# DCP_DC_DC.net
KiCad netlist of a schematic drawn in Altium Designer
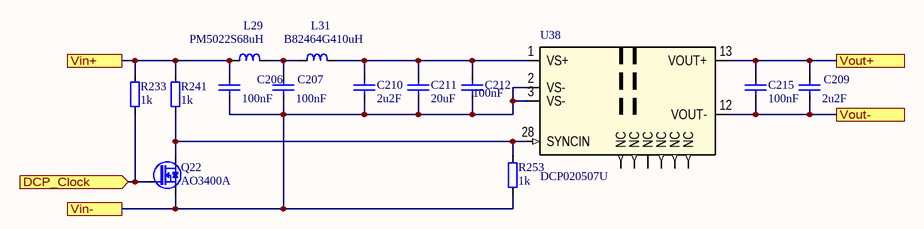
[diagram p0: DCP_DC_DC.SchDoc]

(export (version "E")
  (design (tool "Eeschema 10.0.6"))
  (components
    (comp (ref "C206")
      (value "100nF")
      (footprint "SMD0805CAP")
      (description "Чип конденсатор 0805")
      (fields (field (name "VOLTAGE") "25V") (field (name "TOLERANCE") "20%"))
      (libsource (lib "DDSintLib") (part "C0805"))
    )
    (comp (ref "C207")
      (value "100nF")
      (footprint "SMD0805CAP")
      (description "Чип конденсатор 0805")
      (fields (field (name "VOLTAGE") "25V") (field (name "TOLERANCE") "20%"))
      (libsource (lib "DDSintLib") (part "C0805"))
    )
    (comp (ref "C209")
      (value "2u2F")
      (footprint "SMD0805CAP")
      (description "Чип конденсатор 0805")
      (fields (field (name "VOLTAGE") "25V") (field (name "TOLERANCE") "20%"))
      (libsource (lib "DDSintLib") (part "C0805"))
    )
    (comp (ref "C210")
      (value "2u2F")
      (footprint "SMD0805CAP")
      (description "Чип конденсатор 0805")
      (fields (field (name "VOLTAGE") "25V") (field (name "TOLERANCE") "20%"))
      (libsource (lib "DDSintLib") (part "C0805"))
    )
    (comp (ref "C211")
      (value "20uF")
      (footprint "CAPC1206")
      (description "Чип конденсатор 0805")
      (fields (field (name "VOLTAGE") "16V") (field (name "TOLERANCE") "1%"))
      (libsource (lib "DDSintLib") (part "C1206"))
    )
    (comp (ref "C212")
      (value "100nF")
      (footprint "SMD0805CAP")
      (description "Чип конденсатор 0805")
      (fields (field (name "VOLTAGE") "25V") (field (name "TOLERANCE") "20%"))
      (libsource (lib "DDSintLib") (part "C0805"))
    )
    (comp (ref "C215")
      (value "100nF")
      (footprint "SMD0805CAP")
      (description "Чип конденсатор 0805")
      (fields (field (name "VOLTAGE") "25V") (field (name "TOLERANCE") "20%"))
      (libsource (lib "DDSintLib") (part "C0805"))
    )
    (comp (ref "L29")
      (value "PM5022S68uH")
      (footprint "IND_Bourns_PM5022S")
      (description "SMD Дроссель")
      (fields (field (name "VOLTAGE") "2") (field (name "TOLERANCE") "20%"))
      (libsource (lib "DDS1") (part "IND_BOURNS_PM5022S"))
    )
    (comp (ref "L31")
      (value "B82464G410uH")
      (footprint "IND_COILCRAFT_MSS1038")
      (description "SMD Дроссель")
      (fields (field (name "VOLTAGE") "2") (field (name "TOLERANCE") "20%"))
      (libsource (lib "DDSintLib") (part "B82464G4"))
    )
    (comp (ref "Q22")
      (value "AO3400A")
      (footprint "SOT95P229X119-3N")
      (description "NMOS")
      (fields (field (name "VOLTAGE") "30V"))
      (libsource (lib "DDSintLib") (part "AO3400A"))
    )
    (comp (ref "R233")
      (value "1k")
      (footprint "SMD0805RES")
      (description "Чип резистор 0805")
      (fields (field (name "TOLERANCE") "1%"))
      (libsource (lib "DDSintLib") (part "R0805"))
    )
    (comp (ref "R241")
      (value "1k")
      (footprint "SMD0805RES")
      (description "Чип резистор 0805")
      (fields (field (name "TOLERANCE") "1%"))
      (libsource (lib "DDSintLib") (part "R0805"))
    )
    (comp (ref "R253")
      (value "1k")
      (footprint "SMD0805RES")
      (description "Чип резистор 0805")
      (fields (field (name "TOLERANCE") "1%"))
      (libsource (lib "DDSintLib") (part "R0805"))
    )
    (comp (ref "U38")
      (value "DCP020507U")
      (footprint "SOIC127P1033X265-12_28N")
      (description "DC/DC xxV to isolated  yyV")
      (fields
        (field (name "VOLTAGE") "7V")
        (field (name "COPYRIGHT") "Copyright (C) 2022 Ultra Librarian. All rights reserved.")
      )
      (libsource (lib "DDS1") (part "DCP02xxyyU"))
    )
  )
  (nets
    (net (code "1") (name "/DCP_Clock") (class "Default")
      (node (ref "Q22") (pin "1") (pinfunction "G_1") (pintype "passive"))
      (node (ref "R233") (pin "2") (pinfunction "2_2") (pintype "passive"))
    )
    (net (code "2") (name "/Vin+") (class "Default")
      (node (ref "C206") (pin "2") (pinfunction "2_2") (pintype "passive"))
      (node (ref "L29") (pin "1") (pinfunction "1_1") (pintype "passive"))
      (node (ref "R233") (pin "1") (pinfunction "1_1") (pintype "passive"))
      (node (ref "R241") (pin "1") (pinfunction "1_1") (pintype "passive"))
    )
    (net (code "3") (name "/Vin-") (class "Default")
      (node (ref "C206") (pin "1") (pinfunction "1_1") (pintype "passive"))
      (node (ref "C207") (pin "1") (pinfunction "1_1") (pintype "passive"))
      (node (ref "C210") (pin "1") (pinfunction "1_1") (pintype "passive"))
      (node (ref "C211") (pin "1") (pinfunction "1_1") (pintype "passive"))
      (node (ref "C212") (pin "1") (pinfunction "1_1") (pintype "passive"))
      (node (ref "Q22") (pin "2") (pinfunction "S_2") (pintype "passive"))
      (node (ref "R253") (pin "2") (pinfunction "2_2") (pintype "passive"))
      (node (ref "U38") (pin "2") (pinfunction "VS-_2") (pintype "power_in"))
      (node (ref "U38") (pin "3") (pinfunction "VS-_3") (pintype "power_in"))
    )
    (net (code "4") (name "/Vout+") (class "Default")
      (node (ref "C209") (pin "2") (pinfunction "2_2") (pintype "passive"))
      (node (ref "C215") (pin "2") (pinfunction "2_2") (pintype "passive"))
      (node (ref "U38") (pin "13") (pinfunction "VOUT+_13") (pintype "power_in"))
    )
    (net (code "5") (name "/Vout-") (class "Default")
      (node (ref "C209") (pin "1") (pinfunction "1_1") (pintype "passive"))
      (node (ref "C215") (pin "1") (pinfunction "1_1") (pintype "passive"))
      (node (ref "U38") (pin "12") (pinfunction "VOUT-_12") (pintype "power_in"))
    )
    (net (code "6") (name "Net-(C207-Pad2)") (class "Default")
      (node (ref "C207") (pin "2") (pinfunction "2_2") (pintype "passive"))
      (node (ref "L29") (pin "2") (pinfunction "2_2") (pintype "passive"))
      (node (ref "L31") (pin "1") (pinfunction "1_1") (pintype "passive"))
    )
    (net (code "7") (name "Net-(Q22-D)") (class "Default")
      (node (ref "Q22") (pin "3") (pinfunction "D_3") (pintype "passive"))
      (node (ref "R241") (pin "2") (pinfunction "2_2") (pintype "passive"))
      (node (ref "R253") (pin "1") (pinfunction "1_1") (pintype "passive"))
      (node (ref "U38") (pin "28") (pinfunction "SYNCIN_28") (pintype "input"))
    )
    (net (code "8") (name "Net-(U38-VS+)") (class "Default")
      (node (ref "C210") (pin "2") (pinfunction "2_2") (pintype "passive"))
      (node (ref "C211") (pin "2") (pinfunction "2_2") (pintype "passive"))
      (node (ref "C212") (pin "2") (pinfunction "2_2") (pintype "passive"))
      (node (ref "L31") (pin "2") (pinfunction "2_2") (pintype "passive"))
      (node (ref "U38") (pin "1") (pinfunction "VS+_1") (pintype "power_in"))
    )
    (net (code "9") (name "unconnected-(U38-NC-Pad14)") (class "Default")
      (node (ref "U38") (pin "14") (pinfunction "NC_14") (pintype "output"))
    )
    (net (code "10") (name "unconnected-(U38-NC-Pad15)") (class "Default")
      (node (ref "U38") (pin "15") (pinfunction "NC_15") (pintype "output"))
    )
    (net (code "11") (name "unconnected-(U38-NC-Pad16)") (class "Default")
      (node (ref "U38") (pin "16") (pinfunction "NC_16") (pintype "passive"))
    )
    (net (code "12") (name "unconnected-(U38-NC-Pad17)") (class "Default")
      (node (ref "U38") (pin "17") (pinfunction "NC_17") (pintype "output"))
    )
    (net (code "13") (name "unconnected-(U38-NC-Pad26)") (class "Default")
      (node (ref "U38") (pin "26") (pinfunction "NC_26") (pintype "output"))
    )
    (net (code "14") (name "unconnected-(U38-NC-Pad27)") (class "Default")
      (node (ref "U38") (pin "27") (pinfunction "NC_27") (pintype "output"))
    )
  )
)
